# Sheet1.net
KiCad netlist of a schematic drawn in Altium Designer
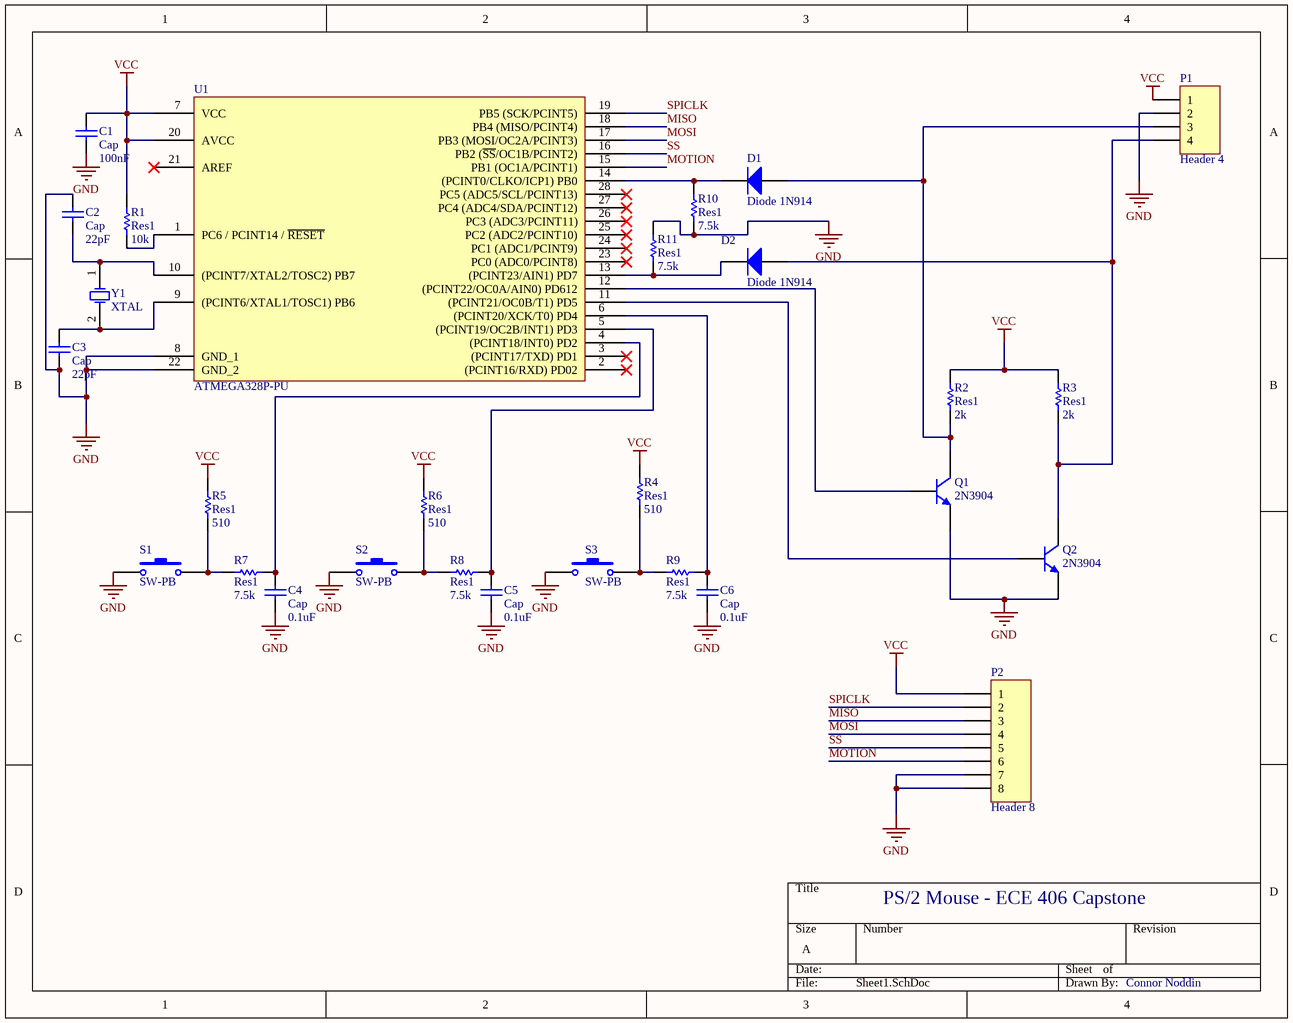
[diagram p0: Sheet1.SchDoc]

(export (version "E")
  (design (tool "Eeschema 10.0.6"))
  (components
    (comp (ref "C1")
      (value "Cap")
      (footprint "RAD-0.3")
      (description "Capacitor")
      (fields (field (name "ALTIUM_VALUE") "100nF") (field (name "PUBLISHER") "Altium Limited"))
      (libsource (lib "Miscellaneous Devices") (part "Cap"))
    )
    (comp (ref "C2")
      (value "Cap")
      (footprint "RAD-0.3")
      (description "Capacitor")
      (fields (field (name "ALTIUM_VALUE") "22pF") (field (name "PUBLISHER") "Altium Limited"))
      (libsource (lib "Miscellaneous Devices") (part "Cap"))
    )
    (comp (ref "C3")
      (value "Cap")
      (footprint "RAD-0.3")
      (description "Capacitor")
      (fields (field (name "ALTIUM_VALUE") "22pF") (field (name "PUBLISHER") "Altium Limited"))
      (libsource (lib "Miscellaneous Devices") (part "Cap"))
    )
    (comp (ref "C4")
      (value "Cap")
      (footprint "RAD-0.3")
      (description "Capacitor")
      (fields (field (name "ALTIUM_VALUE") "0.1uF") (field (name "PUBLISHER") "Altium Limited"))
      (libsource (lib "Miscellaneous Devices") (part "Cap"))
    )
    (comp (ref "C5")
      (value "Cap")
      (footprint "RAD-0.3")
      (description "Capacitor")
      (fields (field (name "ALTIUM_VALUE") "0.1uF") (field (name "PUBLISHER") "Altium Limited"))
      (libsource (lib "Miscellaneous Devices") (part "Cap"))
    )
    (comp (ref "C6")
      (value "Cap")
      (footprint "RAD-0.3")
      (description "Capacitor")
      (fields (field (name "ALTIUM_VALUE") "0.1uF") (field (name "PUBLISHER") "Altium Limited"))
      (libsource (lib "Miscellaneous Devices") (part "Cap"))
    )
    (comp (ref "D1")
      (value "Diode 1N914")
      (footprint "DO-35")
      (description "High Conductance Fast Diode")
      (fields (field (name "PUBLISHER") "Altium Limited"))
      (libsource (lib "Miscellaneous Devices") (part "Diode 1N914"))
    )
    (comp (ref "D2")
      (value "Diode 1N914")
      (footprint "DO-35")
      (description "High Conductance Fast Diode")
      (fields (field (name "PUBLISHER") "Altium Limited"))
      (libsource (lib "Miscellaneous Devices") (part "Diode 1N914"))
    )
    (comp (ref "P1")
      (value "Header 4")
      (footprint "HDR1X4")
      (description "Header, 4-Pin")
      (fields (field (name "PUBLISHER") "Altium Limited"))
      (libsource (lib "Miscellaneous Connectors") (part "Header 4"))
    )
    (comp (ref "P2")
      (value "Header 8")
      (footprint "HDR1X8")
      (description "Header, 8-Pin")
      (fields (field (name "PUBLISHER") "Altium Limited"))
      (libsource (lib "Miscellaneous Connectors") (part "Header 8"))
    )
    (comp (ref "Q1")
      (value "2N3904")
      (footprint "TO-92A")
      (description "NPN General Purpose Amplifier")
      (fields (field (name "PUBLISHER") "Altium Limited"))
      (libsource (lib "Miscellaneous Devices") (part "2N3904"))
    )
    (comp (ref "Q2")
      (value "2N3904")
      (footprint "TO-92A")
      (description "NPN General Purpose Amplifier")
      (fields (field (name "PUBLISHER") "Altium Limited"))
      (libsource (lib "Miscellaneous Devices") (part "2N3904"))
    )
    (comp (ref "R1")
      (value "Res1")
      (footprint "AXIAL-0.3")
      (description "Resistor")
      (fields (field (name "ALTIUM_VALUE") "10k") (field (name "PUBLISHER") "Altium Limited"))
      (libsource (lib "Miscellaneous Devices") (part "Res1"))
    )
    (comp (ref "R2")
      (value "Res1")
      (footprint "AXIAL-0.3")
      (description "Resistor")
      (fields (field (name "ALTIUM_VALUE") "2k") (field (name "PUBLISHER") "Altium Limited"))
      (libsource (lib "Miscellaneous Devices") (part "Res1"))
    )
    (comp (ref "R3")
      (value "Res1")
      (footprint "AXIAL-0.3")
      (description "Resistor")
      (fields (field (name "ALTIUM_VALUE") "2k") (field (name "PUBLISHER") "Altium Limited"))
      (libsource (lib "Miscellaneous Devices") (part "Res1"))
    )
    (comp (ref "R4")
      (value "Res1")
      (footprint "AXIAL-0.3")
      (description "Resistor")
      (fields (field (name "ALTIUM_VALUE") "510") (field (name "PUBLISHER") "Altium Limited"))
      (libsource (lib "Miscellaneous Devices") (part "Res1"))
    )
    (comp (ref "R5")
      (value "Res1")
      (footprint "AXIAL-0.3")
      (description "Resistor")
      (fields (field (name "ALTIUM_VALUE") "510") (field (name "PUBLISHER") "Altium Limited"))
      (libsource (lib "Miscellaneous Devices") (part "Res1"))
    )
    (comp (ref "R6")
      (value "Res1")
      (footprint "AXIAL-0.3")
      (description "Resistor")
      (fields (field (name "ALTIUM_VALUE") "510") (field (name "PUBLISHER") "Altium Limited"))
      (libsource (lib "Miscellaneous Devices") (part "Res1"))
    )
    (comp (ref "R7")
      (value "Res1")
      (footprint "AXIAL-0.3")
      (description "Resistor")
      (fields (field (name "ALTIUM_VALUE") "7.5k") (field (name "PUBLISHER") "Altium Limited"))
      (libsource (lib "Miscellaneous Devices") (part "Res1"))
    )
    (comp (ref "R8")
      (value "Res1")
      (footprint "AXIAL-0.3")
      (description "Resistor")
      (fields (field (name "ALTIUM_VALUE") "7.5k") (field (name "PUBLISHER") "Altium Limited"))
      (libsource (lib "Miscellaneous Devices") (part "Res1"))
    )
    (comp (ref "R9")
      (value "Res1")
      (footprint "AXIAL-0.3")
      (description "Resistor")
      (fields (field (name "ALTIUM_VALUE") "7.5k") (field (name "PUBLISHER") "Altium Limited"))
      (libsource (lib "Miscellaneous Devices") (part "Res1"))
    )
    (comp (ref "R10")
      (value "Res1")
      (footprint "AXIAL-0.3")
      (description "Resistor")
      (fields (field (name "ALTIUM_VALUE") "7.5k") (field (name "PUBLISHER") "Altium Limited"))
      (libsource (lib "Miscellaneous Devices") (part "Res1"))
    )
    (comp (ref "R11")
      (value "Res1")
      (footprint "AXIAL-0.3")
      (description "Resistor")
      (fields (field (name "ALTIUM_VALUE") "7.5k") (field (name "PUBLISHER") "Altium Limited"))
      (libsource (lib "Miscellaneous Devices") (part "Res1"))
    )
    (comp (ref "S1")
      (value "SW-PB")
      (footprint "SPST-2")
      (description "Switch")
      (fields (field (name "PUBLISHER") "Altium Limited"))
      (libsource (lib "Miscellaneous Devices") (part "SW-PB"))
    )
    (comp (ref "S2")
      (value "SW-PB")
      (footprint "SPST-2")
      (description "Switch")
      (fields (field (name "PUBLISHER") "Altium Limited"))
      (libsource (lib "Miscellaneous Devices") (part "SW-PB"))
    )
    (comp (ref "S3")
      (value "SW-PB")
      (footprint "SPST-2")
      (description "Switch")
      (fields (field (name "PUBLISHER") "Altium Limited"))
      (libsource (lib "Miscellaneous Devices") (part "SW-PB"))
    )
    (comp (ref "U1")
      (value "ATMEGA328P-PU")
      (footprint "27_DIP_7.62mm:27_DIP_7.62mm")
      (description "ATMEGA328P-PU; 8 bit Microcontroller AVR 20MHz 1; 32kb Flash; 2kb RAM; I2C SPI 2")
      (fields (field (name "MANUFACTURER") "Microchip / Atmel"))
      (libsource (lib "ATMEGA328P-PU") (part "ATMEGA328P-PU"))
    )
    (comp (ref "Y1")
      (value "XTAL")
      (footprint "DO-35")
      (description "Crystal Oscillator")
      (fields (field (name "PUBLISHER") "Altium Limited"))
      (libsource (lib "Miscellaneous Devices") (part "XTAL"))
    )
  )
  (nets
    (net (code "1") (name "/MISO") (class "Default")
      (node (ref "P2") (pin "3") (pinfunction "3_3") (pintype "passive"))
      (node (ref "U1") (pin "18") (pinfunction "PB4_(MISO/PCINT4)_18") (pintype "passive"))
    )
    (net (code "2") (name "/MOSI") (class "Default")
      (node (ref "P2") (pin "4") (pinfunction "4_4") (pintype "passive"))
      (node (ref "U1") (pin "17") (pinfunction "PB3_(MOSI/OC2A/PCINT3)_17") (pintype "passive"))
    )
    (net (code "3") (name "/MOTION") (class "Default")
      (node (ref "P2") (pin "6") (pinfunction "6_6") (pintype "passive"))
      (node (ref "U1") (pin "15") (pinfunction "PB1_(OC1A/PCINT1)_15") (pintype "passive"))
    )
    (net (code "4") (name "/SPICLK") (class "Default")
      (node (ref "P2") (pin "2") (pinfunction "2_2") (pintype "passive"))
      (node (ref "U1") (pin "19") (pinfunction "PB5_(SCK/PCINT5)_19") (pintype "passive"))
    )
    (net (code "5") (name "/SS") (class "Default")
      (node (ref "P2") (pin "5") (pinfunction "5_5") (pintype "passive"))
      (node (ref "U1") (pin "16") (pinfunction "PB2_(~{SS}/OC1B/PCINT2)_16") (pintype "passive"))
    )
    (net (code "6") (name "GND") (class "Default")
      (node (ref "C1") (pin "2") (pinfunction "2_2") (pintype "passive"))
      (node (ref "C2") (pin "1") (pinfunction "1_1") (pintype "passive"))
      (node (ref "C3") (pin "2") (pinfunction "2_2") (pintype "passive"))
      (node (ref "C4") (pin "1") (pinfunction "1_1") (pintype "passive"))
      (node (ref "C5") (pin "1") (pinfunction "1_1") (pintype "passive"))
      (node (ref "C6") (pin "1") (pinfunction "1_1") (pintype "passive"))
      (node (ref "P1") (pin "2") (pinfunction "2_2") (pintype "passive"))
      (node (ref "P2") (pin "7") (pinfunction "7_7") (pintype "passive"))
      (node (ref "P2") (pin "8") (pinfunction "8_8") (pintype "passive"))
      (node (ref "Q1") (pin "1") (pinfunction "E_1") (pintype "passive"))
      (node (ref "Q2") (pin "1") (pinfunction "E_1") (pintype "passive"))
      (node (ref "R10") (pin "1") (pinfunction "1_1") (pintype "passive"))
      (node (ref "R11") (pin "2") (pinfunction "2_2") (pintype "passive"))
      (node (ref "S1") (pin "1") (pinfunction "1_1") (pintype "passive"))
      (node (ref "S2") (pin "1") (pinfunction "1_1") (pintype "passive"))
      (node (ref "S3") (pin "1") (pinfunction "1_1") (pintype "passive"))
      (node (ref "U1") (pin "22") (pinfunction "GND_2_22") (pintype "passive"))
      (node (ref "U1") (pin "8") (pinfunction "GND_1_8") (pintype "passive"))
    )
    (net (code "7") (name "Net-(D1-A)") (class "Default")
      (node (ref "D1") (pin "1") (pinfunction "A_1") (pintype "passive"))
      (node (ref "P1") (pin "3") (pinfunction "3_3") (pintype "passive"))
      (node (ref "Q1") (pin "3") (pinfunction "C_3") (pintype "passive"))
      (node (ref "R2") (pin "1") (pinfunction "1_1") (pintype "passive"))
    )
    (net (code "8") (name "Net-(D1-K)") (class "Default")
      (node (ref "D1") (pin "2") (pinfunction "K_2") (pintype "passive"))
      (node (ref "R10") (pin "2") (pinfunction "2_2") (pintype "passive"))
      (node (ref "U1") (pin "14") (pinfunction "(PCINT0/CLKO/ICP1)_PB0_14") (pintype "passive"))
    )
    (net (code "9") (name "Net-(D2-A)") (class "Default")
      (node (ref "D2") (pin "1") (pinfunction "A_1") (pintype "passive"))
      (node (ref "P1") (pin "4") (pinfunction "4_4") (pintype "passive"))
      (node (ref "Q2") (pin "3") (pinfunction "C_3") (pintype "passive"))
      (node (ref "R3") (pin "1") (pinfunction "1_1") (pintype "passive"))
    )
    (net (code "10") (name "Net-(D2-K)") (class "Default")
      (node (ref "D2") (pin "2") (pinfunction "K_2") (pintype "passive"))
      (node (ref "R11") (pin "1") (pinfunction "1_1") (pintype "passive"))
      (node (ref "U1") (pin "13") (pinfunction "(PCINT23/AIN1)_PD7_13") (pintype "passive"))
    )
    (net (code "11") (name "Net-(Q1-B)") (class "Default")
      (node (ref "Q1") (pin "2") (pinfunction "B_2") (pintype "passive"))
      (node (ref "U1") (pin "12") (pinfunction "(PCINT22/OC0A/AIN0)_PD612_12") (pintype "passive"))
    )
    (net (code "12") (name "Net-(Q2-B)") (class "Default")
      (node (ref "Q2") (pin "2") (pinfunction "B_2") (pintype "passive"))
      (node (ref "U1") (pin "11") (pinfunction "(PCINT21/OC0B/T1)_PD5_11") (pintype "passive"))
    )
    (net (code "13") (name "Net-(R4-Pad1)") (class "Default")
      (node (ref "R4") (pin "1") (pinfunction "1_1") (pintype "passive"))
      (node (ref "R9") (pin "1") (pinfunction "1_1") (pintype "passive"))
      (node (ref "S3") (pin "2") (pinfunction "2_2") (pintype "passive"))
    )
    (net (code "14") (name "Net-(R5-Pad1)") (class "Default")
      (node (ref "R5") (pin "1") (pinfunction "1_1") (pintype "passive"))
      (node (ref "R7") (pin "1") (pinfunction "1_1") (pintype "passive"))
      (node (ref "S1") (pin "2") (pinfunction "2_2") (pintype "passive"))
    )
    (net (code "15") (name "Net-(R6-Pad1)") (class "Default")
      (node (ref "R6") (pin "1") (pinfunction "1_1") (pintype "passive"))
      (node (ref "R8") (pin "1") (pinfunction "1_1") (pintype "passive"))
      (node (ref "S2") (pin "2") (pinfunction "2_2") (pintype "passive"))
    )
    (net (code "16") (name "Net-(U1-(PCINT6{slash}XTAL1{slash}TOSC1)_PB6)") (class "Default")
      (node (ref "C3") (pin "1") (pinfunction "1_1") (pintype "passive"))
      (node (ref "U1") (pin "9") (pinfunction "(PCINT6/XTAL1/TOSC1)_PB6_9") (pintype "passive"))
      (node (ref "Y1") (pin "2") (pinfunction "OSC2_2") (pintype "passive"))
    )
    (net (code "17") (name "Net-(U1-(PCINT7{slash}XTAL2{slash}TOSC2)_PB7)") (class "Default")
      (node (ref "C2") (pin "2") (pinfunction "2_2") (pintype "passive"))
      (node (ref "U1") (pin "10") (pinfunction "(PCINT7/XTAL2/TOSC2)_PB7_10") (pintype "passive"))
      (node (ref "Y1") (pin "1") (pinfunction "OSC1_1") (pintype "passive"))
    )
    (net (code "18") (name "Net-(U1-(PCINT18{slash}INT0)_PD2)") (class "Default")
      (node (ref "C4") (pin "2") (pinfunction "2_2") (pintype "passive"))
      (node (ref "R7") (pin "2") (pinfunction "2_2") (pintype "passive"))
      (node (ref "U1") (pin "4") (pinfunction "(PCINT18/INT0)_PD2_4") (pintype "passive"))
    )
    (net (code "19") (name "Net-(U1-(PCINT19{slash}OC2B{slash}INT1)_PD3)") (class "Default")
      (node (ref "C5") (pin "2") (pinfunction "2_2") (pintype "passive"))
      (node (ref "R8") (pin "2") (pinfunction "2_2") (pintype "passive"))
      (node (ref "U1") (pin "5") (pinfunction "(PCINT19/OC2B/INT1)_PD3_5") (pintype "passive"))
    )
    (net (code "20") (name "Net-(U1-(PCINT20{slash}XCK{slash}T0)_PD4)") (class "Default")
      (node (ref "C6") (pin "2") (pinfunction "2_2") (pintype "passive"))
      (node (ref "R9") (pin "2") (pinfunction "2_2") (pintype "passive"))
      (node (ref "U1") (pin "6") (pinfunction "(PCINT20/XCK/T0)_PD4_6") (pintype "passive"))
    )
    (net (code "21") (name "Net-(U1-PC6_{slash}_PCINT14_{slash}_~{RESET})") (class "Default")
      (node (ref "R1") (pin "1") (pinfunction "1_1") (pintype "passive"))
      (node (ref "U1") (pin "1") (pinfunction "PC6_/_PCINT14_/_~{RESET}_1") (pintype "passive"))
    )
    (net (code "22") (name "VCC") (class "Default")
      (node (ref "C1") (pin "1") (pinfunction "1_1") (pintype "passive"))
      (node (ref "P1") (pin "1") (pinfunction "1_1") (pintype "passive"))
      (node (ref "P2") (pin "1") (pinfunction "1_1") (pintype "passive"))
      (node (ref "R1") (pin "2") (pinfunction "2_2") (pintype "passive"))
      (node (ref "R2") (pin "2") (pinfunction "2_2") (pintype "passive"))
      (node (ref "R3") (pin "2") (pinfunction "2_2") (pintype "passive"))
      (node (ref "R4") (pin "2") (pinfunction "2_2") (pintype "passive"))
      (node (ref "R5") (pin "2") (pinfunction "2_2") (pintype "passive"))
      (node (ref "R6") (pin "2") (pinfunction "2_2") (pintype "passive"))
      (node (ref "U1") (pin "20") (pinfunction "AVCC_20") (pintype "passive"))
      (node (ref "U1") (pin "7") (pinfunction "VCC_7") (pintype "passive"))
    )
    (net (code "23") (name "unconnected-(U1-(PCINT16{slash}RXD)_PD02-Pad2)") (class "Default")
      (node (ref "U1") (pin "2") (pinfunction "(PCINT16/RXD)_PD02_2") (pintype "passive+no_connect"))
    )
    (net (code "24") (name "unconnected-(U1-(PCINT17{slash}TXD)_PD1-Pad3)") (class "Default")
      (node (ref "U1") (pin "3") (pinfunction "(PCINT17/TXD)_PD1_3") (pintype "passive+no_connect"))
    )
    (net (code "25") (name "unconnected-(U1-AREF-Pad21)") (class "Default")
      (node (ref "U1") (pin "21") (pinfunction "AREF_21") (pintype "passive+no_connect"))
    )
    (net (code "26") (name "unconnected-(U1-PC0_(ADC0{slash}PCINT8)-Pad23)") (class "Default")
      (node (ref "U1") (pin "23") (pinfunction "PC0_(ADC0/PCINT8)_23") (pintype "passive+no_connect"))
    )
    (net (code "27") (name "unconnected-(U1-PC1_(ADC1{slash}PCINT9)-Pad24)") (class "Default")
      (node (ref "U1") (pin "24") (pinfunction "PC1_(ADC1/PCINT9)_24") (pintype "passive+no_connect"))
    )
    (net (code "28") (name "unconnected-(U1-PC2_(ADC2{slash}PCINT10)-Pad25)") (class "Default")
      (node (ref "U1") (pin "25") (pinfunction "PC2_(ADC2/PCINT10)_25") (pintype "passive+no_connect"))
    )
    (net (code "29") (name "unconnected-(U1-PC3_(ADC3{slash}PCINT11)-Pad26)") (class "Default")
      (node (ref "U1") (pin "26") (pinfunction "PC3_(ADC3/PCINT11)_26") (pintype "passive+no_connect"))
    )
    (net (code "30") (name "unconnected-(U1-PC4_(ADC4{slash}SDA{slash}PCINT12)-Pad27)") (class "Default")
      (node (ref "U1") (pin "27") (pinfunction "PC4_(ADC4/SDA/PCINT12)_27") (pintype "passive+no_connect"))
    )
    (net (code "31") (name "unconnected-(U1-PC5_(ADC5{slash}SCL{slash}PCINT13)-Pad28)") (class "Default")
      (node (ref "U1") (pin "28") (pinfunction "PC5_(ADC5/SCL/PCINT13)_28") (pintype "passive+no_connect"))
    )
  )
)
